# 2_cyber60-alps_matrix.net
KiCad netlist of a schematic drawn in Altium Designer
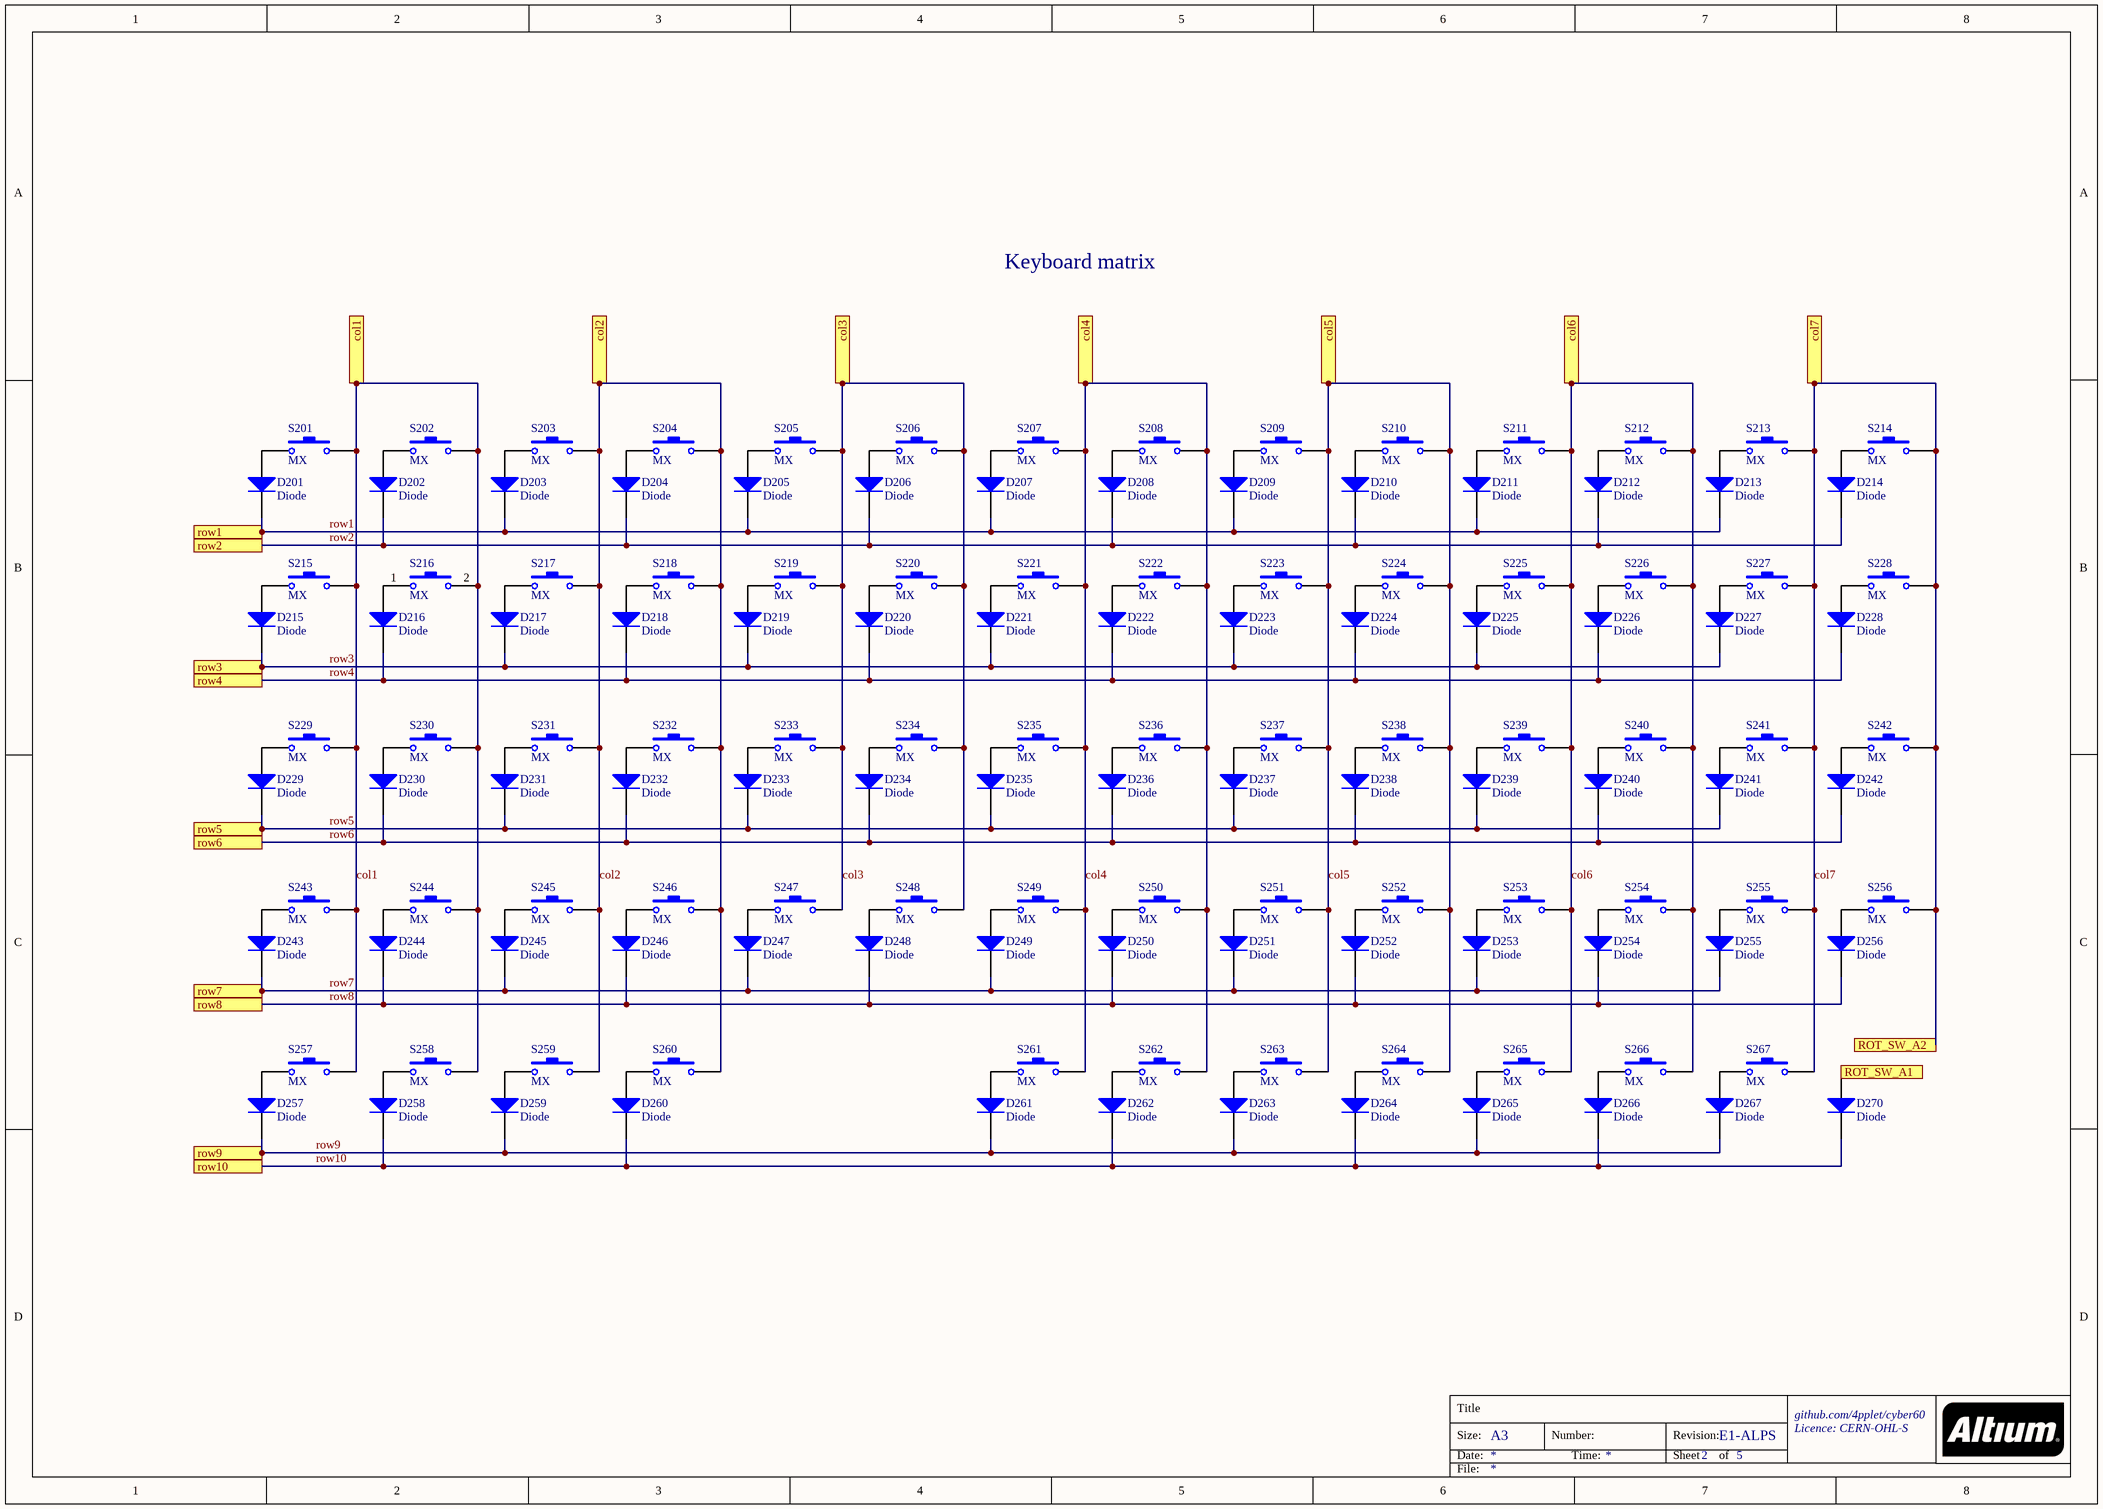
[diagram p0: 2_cyber60-alps_matrix.SchDoc]

(export (version "E")
  (design (tool "Eeschema 10.0.6"))
  (components
    (comp (ref "D201")
      (value "Diode")
      (footprint "SOD-123")
      (description "Default Diode")
      (fields (field (name "LCSC PART #") "C81598") (field (name "MRF.PART") "1N4148W"))
      (libsource (lib "Miscellaneous Devices") (part "Diode"))
    )
    (comp (ref "D202")
      (value "Diode")
      (footprint "SOD-123")
      (description "Default Diode")
      (fields (field (name "LCSC PART #") "C81598") (field (name "MRF.PART") "1N4148W"))
      (libsource (lib "Miscellaneous Devices") (part "Diode"))
    )
    (comp (ref "D203")
      (value "Diode")
      (footprint "SOD-123")
      (description "Default Diode")
      (fields (field (name "LCSC PART #") "C81598") (field (name "MRF.PART") "1N4148W"))
      (libsource (lib "Miscellaneous Devices") (part "Diode"))
    )
    (comp (ref "D204")
      (value "Diode")
      (footprint "SOD-123")
      (description "Default Diode")
      (fields (field (name "LCSC PART #") "C81598") (field (name "MRF.PART") "1N4148W"))
      (libsource (lib "Miscellaneous Devices") (part "Diode"))
    )
    (comp (ref "D205")
      (value "Diode")
      (footprint "SOD-123")
      (description "Default Diode")
      (fields (field (name "LCSC PART #") "C81598") (field (name "MRF.PART") "1N4148W"))
      (libsource (lib "Miscellaneous Devices") (part "Diode"))
    )
    (comp (ref "D206")
      (value "Diode")
      (footprint "SOD-123")
      (description "Default Diode")
      (fields (field (name "LCSC PART #") "C81598") (field (name "MRF.PART") "1N4148W"))
      (libsource (lib "Miscellaneous Devices") (part "Diode"))
    )
    (comp (ref "D207")
      (value "Diode")
      (footprint "SOD-123")
      (description "Default Diode")
      (fields (field (name "LCSC PART #") "C81598") (field (name "MRF.PART") "1N4148W"))
      (libsource (lib "Miscellaneous Devices") (part "Diode"))
    )
    (comp (ref "D208")
      (value "Diode")
      (footprint "SOD-123")
      (description "Default Diode")
      (fields (field (name "LCSC PART #") "C81598") (field (name "MRF.PART") "1N4148W"))
      (libsource (lib "Miscellaneous Devices") (part "Diode"))
    )
    (comp (ref "D209")
      (value "Diode")
      (footprint "SOD-123")
      (description "Default Diode")
      (fields (field (name "LCSC PART #") "C81598") (field (name "MRF.PART") "1N4148W"))
      (libsource (lib "Miscellaneous Devices") (part "Diode"))
    )
    (comp (ref "D210")
      (value "Diode")
      (footprint "SOD-123")
      (description "Default Diode")
      (fields (field (name "LCSC PART #") "C81598") (field (name "MRF.PART") "1N4148W"))
      (libsource (lib "Miscellaneous Devices") (part "Diode"))
    )
    (comp (ref "D211")
      (value "Diode")
      (footprint "SOD-123")
      (description "Default Diode")
      (fields (field (name "LCSC PART #") "C81598") (field (name "MRF.PART") "1N4148W"))
      (libsource (lib "Miscellaneous Devices") (part "Diode"))
    )
    (comp (ref "D212")
      (value "Diode")
      (footprint "SOD-123")
      (description "Default Diode")
      (fields (field (name "LCSC PART #") "C81598") (field (name "MRF.PART") "1N4148W"))
      (libsource (lib "Miscellaneous Devices") (part "Diode"))
    )
    (comp (ref "D213")
      (value "Diode")
      (footprint "SOD-123")
      (description "Default Diode")
      (fields (field (name "LCSC PART #") "C81598") (field (name "MRF.PART") "1N4148W"))
      (libsource (lib "Miscellaneous Devices") (part "Diode"))
    )
    (comp (ref "D214")
      (value "Diode")
      (footprint "SOD-123")
      (description "Default Diode")
      (fields (field (name "LCSC PART #") "C81598") (field (name "MRF.PART") "1N4148W"))
      (libsource (lib "Miscellaneous Devices") (part "Diode"))
    )
    (comp (ref "D215")
      (value "Diode")
      (footprint "SOD-123")
      (description "Default Diode")
      (fields (field (name "LCSC PART #") "C81598") (field (name "MRF.PART") "1N4148W"))
      (libsource (lib "Miscellaneous Devices") (part "Diode"))
    )
    (comp (ref "D216")
      (value "Diode")
      (footprint "SOD-123")
      (description "Default Diode")
      (fields (field (name "LCSC PART #") "C81598") (field (name "MRF.PART") "1N4148W"))
      (libsource (lib "Miscellaneous Devices") (part "Diode"))
    )
    (comp (ref "D217")
      (value "Diode")
      (footprint "SOD-123")
      (description "Default Diode")
      (fields (field (name "LCSC PART #") "C81598") (field (name "MRF.PART") "1N4148W"))
      (libsource (lib "Miscellaneous Devices") (part "Diode"))
    )
    (comp (ref "D218")
      (value "Diode")
      (footprint "SOD-123")
      (description "Default Diode")
      (fields (field (name "LCSC PART #") "C81598") (field (name "MRF.PART") "1N4148W"))
      (libsource (lib "Miscellaneous Devices") (part "Diode"))
    )
    (comp (ref "D219")
      (value "Diode")
      (footprint "SOD-123")
      (description "Default Diode")
      (fields (field (name "LCSC PART #") "C81598") (field (name "MRF.PART") "1N4148W"))
      (libsource (lib "Miscellaneous Devices") (part "Diode"))
    )
    (comp (ref "D220")
      (value "Diode")
      (footprint "SOD-123")
      (description "Default Diode")
      (fields (field (name "LCSC PART #") "C81598") (field (name "MRF.PART") "1N4148W"))
      (libsource (lib "Miscellaneous Devices") (part "Diode"))
    )
    (comp (ref "D221")
      (value "Diode")
      (footprint "SOD-123")
      (description "Default Diode")
      (fields (field (name "LCSC PART #") "C81598") (field (name "MRF.PART") "1N4148W"))
      (libsource (lib "Miscellaneous Devices") (part "Diode"))
    )
    (comp (ref "D222")
      (value "Diode")
      (footprint "SOD-123")
      (description "Default Diode")
      (fields (field (name "LCSC PART #") "C81598") (field (name "MRF.PART") "1N4148W"))
      (libsource (lib "Miscellaneous Devices") (part "Diode"))
    )
    (comp (ref "D223")
      (value "Diode")
      (footprint "SOD-123")
      (description "Default Diode")
      (fields (field (name "LCSC PART #") "C81598") (field (name "MRF.PART") "1N4148W"))
      (libsource (lib "Miscellaneous Devices") (part "Diode"))
    )
    (comp (ref "D224")
      (value "Diode")
      (footprint "SOD-123")
      (description "Default Diode")
      (fields (field (name "LCSC PART #") "C81598") (field (name "MRF.PART") "1N4148W"))
      (libsource (lib "Miscellaneous Devices") (part "Diode"))
    )
    (comp (ref "D225")
      (value "Diode")
      (footprint "SOD-123")
      (description "Default Diode")
      (fields (field (name "LCSC PART #") "C81598") (field (name "MRF.PART") "1N4148W"))
      (libsource (lib "Miscellaneous Devices") (part "Diode"))
    )
    (comp (ref "D226")
      (value "Diode")
      (footprint "SOD-123")
      (description "Default Diode")
      (fields (field (name "LCSC PART #") "C81598") (field (name "MRF.PART") "1N4148W"))
      (libsource (lib "Miscellaneous Devices") (part "Diode"))
    )
    (comp (ref "D227")
      (value "Diode")
      (footprint "SOD-123")
      (description "Default Diode")
      (fields (field (name "LCSC PART #") "C81598") (field (name "MRF.PART") "1N4148W"))
      (libsource (lib "Miscellaneous Devices") (part "Diode"))
    )
    (comp (ref "D228")
      (value "Diode")
      (footprint "SOD-123")
      (description "Default Diode")
      (fields (field (name "LCSC PART #") "C81598") (field (name "MRF.PART") "1N4148W"))
      (libsource (lib "Miscellaneous Devices") (part "Diode"))
    )
    (comp (ref "D229")
      (value "Diode")
      (footprint "SOD-123")
      (description "Default Diode")
      (fields (field (name "LCSC PART #") "C81598") (field (name "MRF.PART") "1N4148W"))
      (libsource (lib "Miscellaneous Devices") (part "Diode"))
    )
    (comp (ref "D230")
      (value "Diode")
      (footprint "SOD-123")
      (description "Default Diode")
      (fields (field (name "LCSC PART #") "C81598") (field (name "MRF.PART") "1N4148W"))
      (libsource (lib "Miscellaneous Devices") (part "Diode"))
    )
    (comp (ref "D231")
      (value "Diode")
      (footprint "SOD-123")
      (description "Default Diode")
      (fields (field (name "LCSC PART #") "C81598") (field (name "MRF.PART") "1N4148W"))
      (libsource (lib "Miscellaneous Devices") (part "Diode"))
    )
    (comp (ref "D232")
      (value "Diode")
      (footprint "SOD-123")
      (description "Default Diode")
      (fields (field (name "LCSC PART #") "C81598") (field (name "MRF.PART") "1N4148W"))
      (libsource (lib "Miscellaneous Devices") (part "Diode"))
    )
    (comp (ref "D233")
      (value "Diode")
      (footprint "SOD-123")
      (description "Default Diode")
      (fields (field (name "LCSC PART #") "C81598") (field (name "MRF.PART") "1N4148W"))
      (libsource (lib "Miscellaneous Devices") (part "Diode"))
    )
    (comp (ref "D234")
      (value "Diode")
      (footprint "SOD-123")
      (description "Default Diode")
      (fields (field (name "LCSC PART #") "C81598") (field (name "MRF.PART") "1N4148W"))
      (libsource (lib "Miscellaneous Devices") (part "Diode"))
    )
    (comp (ref "D235")
      (value "Diode")
      (footprint "SOD-123")
      (description "Default Diode")
      (fields (field (name "LCSC PART #") "C81598") (field (name "MRF.PART") "1N4148W"))
      (libsource (lib "Miscellaneous Devices") (part "Diode"))
    )
    (comp (ref "D236")
      (value "Diode")
      (footprint "SOD-123")
      (description "Default Diode")
      (fields (field (name "LCSC PART #") "C81598") (field (name "MRF.PART") "1N4148W"))
      (libsource (lib "Miscellaneous Devices") (part "Diode"))
    )
    (comp (ref "D237")
      (value "Diode")
      (footprint "SOD-123")
      (description "Default Diode")
      (fields (field (name "LCSC PART #") "C81598") (field (name "MRF.PART") "1N4148W"))
      (libsource (lib "Miscellaneous Devices") (part "Diode"))
    )
    (comp (ref "D238")
      (value "Diode")
      (footprint "SOD-123")
      (description "Default Diode")
      (fields (field (name "LCSC PART #") "C81598") (field (name "MRF.PART") "1N4148W"))
      (libsource (lib "Miscellaneous Devices") (part "Diode"))
    )
    (comp (ref "D239")
      (value "Diode")
      (footprint "SOD-123")
      (description "Default Diode")
      (fields (field (name "LCSC PART #") "C81598") (field (name "MRF.PART") "1N4148W"))
      (libsource (lib "Miscellaneous Devices") (part "Diode"))
    )
    (comp (ref "D240")
      (value "Diode")
      (footprint "SOD-123")
      (description "Default Diode")
      (fields (field (name "LCSC PART #") "C81598") (field (name "MRF.PART") "1N4148W"))
      (libsource (lib "Miscellaneous Devices") (part "Diode"))
    )
    (comp (ref "D241")
      (value "Diode")
      (footprint "SOD-123")
      (description "Default Diode")
      (fields (field (name "LCSC PART #") "C81598") (field (name "MRF.PART") "1N4148W"))
      (libsource (lib "Miscellaneous Devices") (part "Diode"))
    )
    (comp (ref "D242")
      (value "Diode")
      (footprint "SOD-123")
      (description "Default Diode")
      (fields (field (name "LCSC PART #") "C81598") (field (name "MRF.PART") "1N4148W"))
      (libsource (lib "Miscellaneous Devices") (part "Diode"))
    )
    (comp (ref "D243")
      (value "Diode")
      (footprint "SOD-123")
      (description "Default Diode")
      (fields (field (name "LCSC PART #") "C81598") (field (name "MRF.PART") "1N4148W"))
      (libsource (lib "Miscellaneous Devices") (part "Diode"))
    )
    (comp (ref "D244")
      (value "Diode")
      (footprint "SOD-123")
      (description "Default Diode")
      (fields (field (name "LCSC PART #") "C81598") (field (name "MRF.PART") "1N4148W"))
      (libsource (lib "Miscellaneous Devices") (part "Diode"))
    )
    (comp (ref "D245")
      (value "Diode")
      (footprint "SOD-123")
      (description "Default Diode")
      (fields (field (name "LCSC PART #") "C81598") (field (name "MRF.PART") "1N4148W"))
      (libsource (lib "Miscellaneous Devices") (part "Diode"))
    )
    (comp (ref "D246")
      (value "Diode")
      (footprint "SOD-123")
      (description "Default Diode")
      (fields (field (name "LCSC PART #") "C81598") (field (name "MRF.PART") "1N4148W"))
      (libsource (lib "Miscellaneous Devices") (part "Diode"))
    )
    (comp (ref "D247")
      (value "Diode")
      (footprint "SOD-123")
      (description "Default Diode")
      (fields (field (name "LCSC PART #") "C81598") (field (name "MRF.PART") "1N4148W"))
      (libsource (lib "Miscellaneous Devices") (part "Diode"))
    )
    (comp (ref "D248")
      (value "Diode")
      (footprint "SOD-123")
      (description "Default Diode")
      (fields (field (name "LCSC PART #") "C81598") (field (name "MRF.PART") "1N4148W"))
      (libsource (lib "Miscellaneous Devices") (part "Diode"))
    )
    (comp (ref "D249")
      (value "Diode")
      (footprint "SOD-123")
      (description "Default Diode")
      (fields (field (name "LCSC PART #") "C81598") (field (name "MRF.PART") "1N4148W"))
      (libsource (lib "Miscellaneous Devices") (part "Diode"))
    )
    (comp (ref "D250")
      (value "Diode")
      (footprint "SOD-123")
      (description "Default Diode")
      (fields (field (name "LCSC PART #") "C81598") (field (name "MRF.PART") "1N4148W"))
      (libsource (lib "Miscellaneous Devices") (part "Diode"))
    )
    (comp (ref "D251")
      (value "Diode")
      (footprint "SOD-123")
      (description "Default Diode")
      (fields (field (name "LCSC PART #") "C81598") (field (name "MRF.PART") "1N4148W"))
      (libsource (lib "Miscellaneous Devices") (part "Diode"))
    )
    (comp (ref "D252")
      (value "Diode")
      (footprint "SOD-123")
      (description "Default Diode")
      (fields (field (name "LCSC PART #") "C81598") (field (name "MRF.PART") "1N4148W"))
      (libsource (lib "Miscellaneous Devices") (part "Diode"))
    )
    (comp (ref "D253")
      (value "Diode")
      (footprint "SOD-123")
      (description "Default Diode")
      (fields (field (name "LCSC PART #") "C81598") (field (name "MRF.PART") "1N4148W"))
      (libsource (lib "Miscellaneous Devices") (part "Diode"))
    )
    (comp (ref "D254")
      (value "Diode")
      (footprint "SOD-123")
      (description "Default Diode")
      (fields (field (name "LCSC PART #") "C81598") (field (name "MRF.PART") "1N4148W"))
      (libsource (lib "Miscellaneous Devices") (part "Diode"))
    )
    (comp (ref "D255")
      (value "Diode")
      (footprint "SOD-123")
      (description "Default Diode")
      (fields (field (name "LCSC PART #") "C81598") (field (name "MRF.PART") "1N4148W"))
      (libsource (lib "Miscellaneous Devices") (part "Diode"))
    )
    (comp (ref "D256")
      (value "Diode")
      (footprint "SOD-123")
      (description "Default Diode")
      (fields (field (name "LCSC PART #") "C81598") (field (name "MRF.PART") "1N4148W"))
      (libsource (lib "Miscellaneous Devices") (part "Diode"))
    )
    (comp (ref "D257")
      (value "Diode")
      (footprint "SOD-123")
      (description "Default Diode")
      (fields (field (name "LCSC PART #") "C81598") (field (name "MRF.PART") "1N4148W"))
      (libsource (lib "Miscellaneous Devices") (part "Diode"))
    )
    (comp (ref "D258")
      (value "Diode")
      (footprint "SOD-123")
      (description "Default Diode")
      (fields (field (name "LCSC PART #") "C81598") (field (name "MRF.PART") "1N4148W"))
      (libsource (lib "Miscellaneous Devices") (part "Diode"))
    )
    (comp (ref "D259")
      (value "Diode")
      (footprint "SOD-123")
      (description "Default Diode")
      (fields (field (name "LCSC PART #") "C81598") (field (name "MRF.PART") "1N4148W"))
      (libsource (lib "Miscellaneous Devices") (part "Diode"))
    )
    (comp (ref "D260")
      (value "Diode")
      (footprint "SOD-123")
      (description "Default Diode")
      (fields (field (name "LCSC PART #") "C81598") (field (name "MRF.PART") "1N4148W"))
      (libsource (lib "Miscellaneous Devices") (part "Diode"))
    )
    (comp (ref "D261")
      (value "Diode")
      (footprint "SOD-123")
      (description "Default Diode")
      (fields (field (name "LCSC PART #") "C81598") (field (name "MRF.PART") "1N4148W"))
      (libsource (lib "Miscellaneous Devices") (part "Diode"))
    )
    (comp (ref "D262")
      (value "Diode")
      (footprint "SOD-123")
      (description "Default Diode")
      (fields (field (name "LCSC PART #") "C81598") (field (name "MRF.PART") "1N4148W"))
      (libsource (lib "Miscellaneous Devices") (part "Diode"))
    )
    (comp (ref "D263")
      (value "Diode")
      (footprint "SOD-123")
      (description "Default Diode")
      (fields (field (name "LCSC PART #") "C81598") (field (name "MRF.PART") "1N4148W"))
      (libsource (lib "Miscellaneous Devices") (part "Diode"))
    )
    (comp (ref "D264")
      (value "Diode")
      (footprint "SOD-123")
      (description "Default Diode")
      (fields (field (name "LCSC PART #") "C81598") (field (name "MRF.PART") "1N4148W"))
      (libsource (lib "Miscellaneous Devices") (part "Diode"))
    )
    (comp (ref "D265")
      (value "Diode")
      (footprint "SOD-123")
      (description "Default Diode")
      (fields (field (name "LCSC PART #") "C81598") (field (name "MRF.PART") "1N4148W"))
      (libsource (lib "Miscellaneous Devices") (part "Diode"))
    )
    (comp (ref "D266")
      (value "Diode")
      (footprint "SOD-123")
      (description "Default Diode")
      (fields (field (name "LCSC PART #") "C81598") (field (name "MRF.PART") "1N4148W"))
      (libsource (lib "Miscellaneous Devices") (part "Diode"))
    )
    (comp (ref "D267")
      (value "Diode")
      (footprint "SOD-123")
      (description "Default Diode")
      (fields (field (name "LCSC PART #") "C81598") (field (name "MRF.PART") "1N4148W"))
      (libsource (lib "Miscellaneous Devices") (part "Diode"))
    )
    (comp (ref "D270")
      (value "Diode")
      (footprint "SOD-123")
      (description "Default Diode")
      (fields (field (name "LCSC PART #") "C81598") (field (name "MRF.PART") "1N4148W"))
      (libsource (lib "Miscellaneous Devices") (part "Diode"))
    )
    (comp (ref "S201")
      (value "MX")
      (footprint "Alps-switch - switched pol")
      (description "Switch")
      (libsource (lib "Miscellaneous Devices") (part "SW-PB"))
    )
    (comp (ref "S202")
      (value "MX")
      (footprint "Alps-switch - switched pol")
      (description "Switch")
      (libsource (lib "Miscellaneous Devices") (part "SW-PB"))
    )
    (comp (ref "S203")
      (value "MX")
      (footprint "Alps-switch - switched pol")
      (description "Switch")
      (libsource (lib "Miscellaneous Devices") (part "SW-PB"))
    )
    (comp (ref "S204")
      (value "MX")
      (footprint "Alps-switch")
      (description "Switch")
      (libsource (lib "Miscellaneous Devices") (part "SW-PB"))
    )
    (comp (ref "S205")
      (value "MX")
      (footprint "Alps-switch - switched pol")
      (description "Switch")
      (libsource (lib "Miscellaneous Devices") (part "SW-PB"))
    )
    (comp (ref "S206")
      (value "MX")
      (footprint "Alps-switch - switched pol")
      (description "Switch")
      (libsource (lib "Miscellaneous Devices") (part "SW-PB"))
    )
    (comp (ref "S207")
      (value "MX")
      (footprint "Alps-switch - switched pol")
      (description "Switch")
      (libsource (lib "Miscellaneous Devices") (part "SW-PB"))
    )
    (comp (ref "S208")
      (value "MX")
      (footprint "Alps-switch - switched pol")
      (description "Switch")
      (libsource (lib "Miscellaneous Devices") (part "SW-PB"))
    )
    (comp (ref "S209")
      (value "MX")
      (footprint "Alps-switch - switched pol")
      (description "Switch")
      (libsource (lib "Miscellaneous Devices") (part "SW-PB"))
    )
    (comp (ref "S210")
      (value "MX")
      (footprint "Alps-switch - switched pol")
      (description "Switch")
      (libsource (lib "Miscellaneous Devices") (part "SW-PB"))
    )
    (comp (ref "S211")
      (value "MX")
      (footprint "Alps-switch - switched pol")
      (description "Switch")
      (libsource (lib "Miscellaneous Devices") (part "SW-PB"))
    )
    (comp (ref "S212")
      (value "MX")
      (footprint "Alps-switch - switched pol")
      (description "Switch")
      (libsource (lib "Miscellaneous Devices") (part "SW-PB"))
    )
    (comp (ref "S213")
      (value "MX")
      (footprint "Alps-switch - switched pol")
      (description "Switch")
      (libsource (lib "Miscellaneous Devices") (part "SW-PB"))
    )
    (comp (ref "S214")
      (value "MX")
      (footprint "Alps-switch - switched pol")
      (description "Switch")
      (libsource (lib "Miscellaneous Devices") (part "SW-PB"))
    )
    (comp (ref "S215")
      (value "MX")
      (footprint "Alps-switch - switched pol")
      (description "TAB")
      (libsource (lib "Miscellaneous Devices") (part "SW-PB"))
    )
    (comp (ref "S216")
      (value "MX")
      (footprint "Alps-switch - switched pol")
      (description "Switch")
      (libsource (lib "") (part "SW-PB_1"))
    )
    (comp (ref "S217")
      (value "MX")
      (footprint "Alps-switch - switched pol")
      (description "Switch")
      (libsource (lib "Miscellaneous Devices") (part "SW-PB"))
    )
    (comp (ref "S218")
      (value "MX")
      (footprint "Alps-switch - switched pol")
      (description "Switch")
      (libsource (lib "Miscellaneous Devices") (part "SW-PB"))
    )
    (comp (ref "S219")
      (value "MX")
      (footprint "Alps-switch - switched pol")
      (description "Switch")
      (libsource (lib "Miscellaneous Devices") (part "SW-PB"))
    )
    (comp (ref "S220")
      (value "MX")
      (footprint "Alps-switch")
      (description "Switch")
      (libsource (lib "Miscellaneous Devices") (part "SW-PB"))
    )
    (comp (ref "S221")
      (value "MX")
      (footprint "Alps-switch - switched pol")
      (description "Switch")
      (libsource (lib "Miscellaneous Devices") (part "SW-PB"))
    )
    (comp (ref "S222")
      (value "MX")
      (footprint "Alps-switch - switched pol")
      (description "Switch")
      (libsource (lib "Miscellaneous Devices") (part "SW-PB"))
    )
    (comp (ref "S223")
      (value "MX")
      (footprint "Alps-switch - switched pol")
      (description "Switch")
      (libsource (lib "Miscellaneous Devices") (part "SW-PB"))
    )
    (comp (ref "S224")
      (value "MX")
      (footprint "Alps-switch - switched pol")
      (description "Switch")
      (libsource (lib "Miscellaneous Devices") (part "SW-PB"))
    )
    (comp (ref "S225")
      (value "MX")
      (footprint "Alps-switch - switched pol")
      (description "Switch")
      (libsource (lib "Miscellaneous Devices") (part "SW-PB"))
    )
    (comp (ref "S226")
      (value "MX")
      (footprint "Alps-switch")
      (description "Switch")
      (libsource (lib "Miscellaneous Devices") (part "SW-PB"))
    )
    (comp (ref "S227")
      (value "MX")
      (footprint "Alps-switch")
      (description "Switch")
      (libsource (lib "Miscellaneous Devices") (part "SW-PB"))
    )
    (comp (ref "S228")
      (value "MX")
      (footprint "ALPS-switch - backspace")
      (description "Switch")
      (libsource (lib "Miscellaneous Devices") (part "SW-PB"))
    )
    (comp (ref "S229")
      (value "MX")
      (footprint "ALPS-switch - CAPS")
      (description "Switch")
      (libsource (lib "Miscellaneous Devices") (part "SW-PB"))
    )
    (comp (ref "S230")
      (value "MX")
      (footprint "Alps-switch - switched pol")
      (description "Switch")
      (libsource (lib "Miscellaneous Devices") (part "SW-PB"))
    )
    (comp (ref "S231")
      (value "MX")
      (footprint "Alps-switch - switched pol")
      (description "Switch")
      (libsource (lib "Miscellaneous Devices") (part "SW-PB"))
    )
    (comp (ref "S232")
      (value "MX")
      (footprint "Alps-switch - switched pol")
      (description "Switch")
      (libsource (lib "Miscellaneous Devices") (part "SW-PB"))
    )
    (comp (ref "S233")
      (value "MX")
      (footprint "Alps-switch - switched pol")
      (description "Switch")
      (libsource (lib "Miscellaneous Devices") (part "SW-PB"))
    )
    (comp (ref "S234")
      (value "MX")
      (footprint "Alps-switch")
      (description "Switch")
      (libsource (lib "Miscellaneous Devices") (part "SW-PB"))
    )
    (comp (ref "S235")
      (value "MX")
      (footprint "Alps-switch - switched pol")
      (description "Switch")
      (libsource (lib "Miscellaneous Devices") (part "SW-PB"))
    )
    (comp (ref "S236")
      (value "MX")
      (footprint "Alps-switch - switched pol")
      (description "Switch")
      (libsource (lib "Miscellaneous Devices") (part "SW-PB"))
    )
    (comp (ref "S237")
      (value "MX")
      (footprint "Alps-switch - switched pol")
      (description "Switch")
      (libsource (lib "Miscellaneous Devices") (part "SW-PB"))
    )
    (comp (ref "S238")
      (value "MX")
      (footprint "Alps-switch - switched pol")
      (description "Switch")
      (libsource (lib "Miscellaneous Devices") (part "SW-PB"))
    )
    (comp (ref "S239")
      (value "MX")
      (footprint "Alps-switch")
      (description "Switch")
      (libsource (lib "Miscellaneous Devices") (part "SW-PB"))
    )
    (comp (ref "S240")
      (value "MX")
      (footprint "Alps-switch - switched pol")
      (description "Switch")
      (libsource (lib "Miscellaneous Devices") (part "SW-PB"))
    )
    (comp (ref "S241")
      (value "MX")
      (footprint "Alps-switch")
      (description "Switch")
      (libsource (lib "Miscellaneous Devices") (part "SW-PB"))
    )
    (comp (ref "S242")
      (value "MX")
      (footprint "ALPS-switch - 1.5U")
      (description "Switch")
      (libsource (lib "Miscellaneous Devices") (part "SW-PB"))
    )
    (comp (ref "S243")
      (value "MX")
      (footprint "ALPS-switch - Left shift v2")
      (description "Switch")
      (libsource (lib "Miscellaneous Devices") (part "SW-PB"))
    )
    (comp (ref "S244")
      (value "MX")
      (footprint "Alps-switch - switched pol")
      (description "Switch")
      (libsource (lib "Miscellaneous Devices") (part "SW-PB"))
    )
    (comp (ref "S245")
      (value "MX")
      (footprint "Alps-switch - switched pol")
      (description "Switch")
      (libsource (lib "Miscellaneous Devices") (part "SW-PB"))
    )
    (comp (ref "S246")
      (value "MX")
      (footprint "Alps-switch - switched pol")
      (description "Switch")
      (libsource (lib "Miscellaneous Devices") (part "SW-PB"))
    )
    (comp (ref "S247")
      (value "MX")
      (footprint "Alps-switch - switched pol")
      (description "Switch")
      (libsource (lib "Miscellaneous Devices") (part "SW-PB"))
    )
    (comp (ref "S248")
      (value "MX")
      (footprint "Alps-switch")
      (description "Switch")
      (libsource (lib "Miscellaneous Devices") (part "SW-PB"))
    )
    (comp (ref "S249")
      (value "MX")
      (footprint "Alps-switch - switched pol")
      (description "Switch")
      (libsource (lib "Miscellaneous Devices") (part "SW-PB"))
    )
    (comp (ref "S250")
      (value "MX")
      (footprint "Alps-switch - switched pol")
      (description "Switch")
      (libsource (lib "Miscellaneous Devices") (part "SW-PB"))
    )
    (comp (ref "S251")
      (value "MX")
      (footprint "Alps-switch - switched pol")
      (description "Switch")
      (libsource (lib "Miscellaneous Devices") (part "SW-PB"))
    )
    (comp (ref "S252")
      (value "MX")
      (footprint "Alps-switch - switched pol")
      (description "Switch")
      (libsource (lib "Miscellaneous Devices") (part "SW-PB"))
    )
    (comp (ref "S253")
      (value "MX")
      (footprint "Alps-switch - switched pol")
      (description "Switch")
      (libsource (lib "Miscellaneous Devices") (part "SW-PB"))
    )
    (comp (ref "S254")
      (value "MX")
      (footprint "Alps-switch - switched pol")
      (description "Switch")
      (libsource (lib "Miscellaneous Devices") (part "SW-PB"))
    )
    (comp (ref "S255")
      (value "MX")
      (footprint "Alps-switch")
      (description "Switch")
      (libsource (lib "Miscellaneous Devices") (part "SW-PB"))
    )
    (comp (ref "S256")
      (value "MX")
      (footprint "ALPS-switch - Enter - rotated stab")
      (description "Switch")
      (libsource (lib "Miscellaneous Devices") (part "SW-PB"))
    )
    (comp (ref "S257")
      (value "MX")
      (footprint "ALPS-switch - 1.5u MOD-L")
      (description "Switch")
      (libsource (lib "Miscellaneous Devices") (part "SW-PB"))
    )
    (comp (ref "S258")
      (value "MX")
      (footprint "ALPS-switch - L_WIN - V3")
      (description "Switch")
      (libsource (lib "Miscellaneous Devices") (part "SW-PB"))
    )
    (comp (ref "S259")
      (value "MX")
      (footprint "ALPS-SWITCH - L_ALT - V3")
      (description "Switch")
      (libsource (lib "Miscellaneous Devices") (part "SW-PB"))
    )
    (comp (ref "S260")
      (value "MX")
      (footprint "ALPS-switch - 2.75U - Rotated stab")
      (description "Switch")
      (libsource (lib "Miscellaneous Devices") (part "SW-PB"))
    )
    (comp (ref "S261")
      (value "MX")
      (footprint "ALPS-switch - Space_V2")
      (description "Switch")
      (libsource (lib "Miscellaneous Devices") (part "SW-PB"))
    )
    (comp (ref "S262")
      (value "MX")
      (footprint "ALPS-switch - 2.75U - Rotated stab")
      (description "Switch")
      (libsource (lib "Miscellaneous Devices") (part "SW-PB"))
    )
    (comp (ref "S263")
      (value "MX")
      (footprint "Alps-switch - switched pol")
      (description "Switch")
      (libsource (lib "Miscellaneous Devices") (part "SW-PB"))
    )
    (comp (ref "S264")
      (value "MX")
      (footprint "ALPS-SWITCH - R_ALT - V3")
      (description "Switch")
      (libsource (lib "Miscellaneous Devices") (part "SW-PB"))
    )
    (comp (ref "S265")
      (value "MX")
      (footprint "ALPS-switch - R_WIN V3")
      (description "Switch")
      (libsource (lib "Miscellaneous Devices") (part "SW-PB"))
    )
    (comp (ref "S266")
      (value "MX")
      (footprint "ALPS-switch - 1.5u MOD-R")
      (description "Switch")
      (libsource (lib "Miscellaneous Devices") (part "SW-PB"))
    )
    (comp (ref "S267")
      (value "MX")
      (footprint "ALPS-switch - right shift - stabs")
      (description "Switch")
      (libsource (lib "Miscellaneous Devices") (part "SW-PB"))
    )
  )
  (nets
    (net (code "1") (name "/ROT_SW_A1") (class "Default")
      (node (ref "D270") (pin "1") (pinfunction "A_1") (pintype "passive"))
    )
    (net (code "2") (name "/col1") (class "Default")
      (node (ref "S201") (pin "2") (pinfunction "2_2") (pintype "passive"))
      (node (ref "S202") (pin "2") (pinfunction "2_2") (pintype "passive"))
      (node (ref "S215") (pin "2") (pinfunction "2_2") (pintype "passive"))
      (node (ref "S216") (pin "2") (pinfunction "2_2") (pintype "passive"))
      (node (ref "S229") (pin "2") (pinfunction "2_2") (pintype "passive"))
      (node (ref "S230") (pin "2") (pinfunction "2_2") (pintype "passive"))
      (node (ref "S243") (pin "2") (pinfunction "2_2") (pintype "passive"))
      (node (ref "S244") (pin "2") (pinfunction "2_2") (pintype "passive"))
      (node (ref "S257") (pin "1") (pinfunction "1_1") (pintype "passive"))
      (node (ref "S258") (pin "2") (pinfunction "2_2") (pintype "passive"))
    )
    (net (code "3") (name "/col2") (class "Default")
      (node (ref "S203") (pin "2") (pinfunction "2_2") (pintype "passive"))
      (node (ref "S204") (pin "2") (pinfunction "2_2") (pintype "passive"))
      (node (ref "S217") (pin "2") (pinfunction "2_2") (pintype "passive"))
      (node (ref "S218") (pin "2") (pinfunction "2_2") (pintype "passive"))
      (node (ref "S231") (pin "2") (pinfunction "2_2") (pintype "passive"))
      (node (ref "S232") (pin "2") (pinfunction "2_2") (pintype "passive"))
      (node (ref "S245") (pin "2") (pinfunction "2_2") (pintype "passive"))
      (node (ref "S246") (pin "2") (pinfunction "2_2") (pintype "passive"))
      (node (ref "S259") (pin "2") (pinfunction "2_2") (pintype "passive"))
      (node (ref "S260") (pin "2") (pinfunction "2_2") (pintype "passive"))
    )
    (net (code "4") (name "/col3") (class "Default")
      (node (ref "S205") (pin "2") (pinfunction "2_2") (pintype "passive"))
      (node (ref "S206") (pin "2") (pinfunction "2_2") (pintype "passive"))
      (node (ref "S219") (pin "2") (pinfunction "2_2") (pintype "passive"))
      (node (ref "S220") (pin "2") (pinfunction "2_2") (pintype "passive"))
      (node (ref "S233") (pin "2") (pinfunction "2_2") (pintype "passive"))
      (node (ref "S234") (pin "2") (pinfunction "2_2") (pintype "passive"))
      (node (ref "S247") (pin "2") (pinfunction "2_2") (pintype "passive"))
      (node (ref "S248") (pin "2") (pinfunction "2_2") (pintype "passive"))
    )
    (net (code "5") (name "/col4") (class "Default")
      (node (ref "S207") (pin "2") (pinfunction "2_2") (pintype "passive"))
      (node (ref "S208") (pin "2") (pinfunction "2_2") (pintype "passive"))
      (node (ref "S221") (pin "2") (pinfunction "2_2") (pintype "passive"))
      (node (ref "S222") (pin "2") (pinfunction "2_2") (pintype "passive"))
      (node (ref "S235") (pin "2") (pinfunction "2_2") (pintype "passive"))
      (node (ref "S236") (pin "2") (pinfunction "2_2") (pintype "passive"))
      (node (ref "S249") (pin "2") (pinfunction "2_2") (pintype "passive"))
      (node (ref "S250") (pin "2") (pinfunction "2_2") (pintype "passive"))
      (node (ref "S261") (pin "1") (pinfunction "1_1") (pintype "passive"))
      (node (ref "S262") (pin "2") (pinfunction "2_2") (pintype "passive"))
    )
    (net (code "6") (name "/col5") (class "Default")
      (node (ref "S209") (pin "2") (pinfunction "2_2") (pintype "passive"))
      (node (ref "S210") (pin "2") (pinfunction "2_2") (pintype "passive"))
      (node (ref "S223") (pin "2") (pinfunction "2_2") (pintype "passive"))
      (node (ref "S224") (pin "2") (pinfunction "2_2") (pintype "passive"))
      (node (ref "S237") (pin "2") (pinfunction "2_2") (pintype "passive"))
      (node (ref "S238") (pin "2") (pinfunction "2_2") (pintype "passive"))
      (node (ref "S251") (pin "2") (pinfunction "2_2") (pintype "passive"))
      (node (ref "S252") (pin "2") (pinfunction "2_2") (pintype "passive"))
      (node (ref "S263") (pin "2") (pinfunction "2_2") (pintype "passive"))
      (node (ref "S264") (pin "1") (pinfunction "1_1") (pintype "passive"))
    )
    (net (code "7") (name "/col6") (class "Default")
      (node (ref "S211") (pin "2") (pinfunction "2_2") (pintype "passive"))
      (node (ref "S212") (pin "2") (pinfunction "2_2") (pintype "passive"))
      (node (ref "S225") (pin "2") (pinfunction "2_2") (pintype "passive"))
      (node (ref "S226") (pin "2") (pinfunction "2_2") (pintype "passive"))
      (node (ref "S239") (pin "2") (pinfunction "2_2") (pintype "passive"))
      (node (ref "S240") (pin "2") (pinfunction "2_2") (pintype "passive"))
      (node (ref "S253") (pin "2") (pinfunction "2_2") (pintype "passive"))
      (node (ref "S254") (pin "2") (pinfunction "2_2") (pintype "passive"))
      (node (ref "S265") (pin "2") (pinfunction "2_2") (pintype "passive"))
      (node (ref "S266") (pin "2") (pinfunction "2_2") (pintype "passive"))
    )
    (net (code "8") (name "/col7") (class "Default")
      (node (ref "S213") (pin "2") (pinfunction "2_2") (pintype "passive"))
      (node (ref "S214") (pin "2") (pinfunction "2_2") (pintype "passive"))
      (node (ref "S227") (pin "2") (pinfunction "2_2") (pintype "passive"))
      (node (ref "S228") (pin "1") (pinfunction "1_1") (pintype "passive"))
      (node (ref "S241") (pin "2") (pinfunction "2_2") (pintype "passive"))
      (node (ref "S242") (pin "2") (pinfunction "2_2") (pintype "passive"))
      (node (ref "S255") (pin "2") (pinfunction "2_2") (pintype "passive"))
      (node (ref "S256") (pin "2") (pinfunction "2_2") (pintype "passive"))
      (node (ref "S267") (pin "1") (pinfunction "1_1") (pintype "passive"))
    )
    (net (code "9") (name "/row1") (class "Default")
      (node (ref "D201") (pin "2") (pinfunction "K_2") (pintype "passive"))
      (node (ref "D203") (pin "2") (pinfunction "K_2") (pintype "passive"))
      (node (ref "D205") (pin "2") (pinfunction "K_2") (pintype "passive"))
      (node (ref "D207") (pin "2") (pinfunction "K_2") (pintype "passive"))
      (node (ref "D209") (pin "2") (pinfunction "K_2") (pintype "passive"))
      (node (ref "D211") (pin "2") (pinfunction "K_2") (pintype "passive"))
      (node (ref "D213") (pin "2") (pinfunction "K_2") (pintype "passive"))
    )
    (net (code "10") (name "/row2") (class "Default")
      (node (ref "D202") (pin "2") (pinfunction "K_2") (pintype "passive"))
      (node (ref "D204") (pin "2") (pinfunction "K_2") (pintype "passive"))
      (node (ref "D206") (pin "2") (pinfunction "K_2") (pintype "passive"))
      (node (ref "D208") (pin "2") (pinfunction "K_2") (pintype "passive"))
      (node (ref "D210") (pin "2") (pinfunction "K_2") (pintype "passive"))
      (node (ref "D212") (pin "2") (pinfunction "K_2") (pintype "passive"))
      (node (ref "D214") (pin "2") (pinfunction "K_2") (pintype "passive"))
    )
    (net (code "11") (name "/row3") (class "Default")
      (node (ref "D215") (pin "2") (pinfunction "K_2") (pintype "passive"))
      (node (ref "D217") (pin "2") (pinfunction "K_2") (pintype "passive"))
      (node (ref "D219") (pin "2") (pinfunction "K_2") (pintype "passive"))
      (node (ref "D221") (pin "2") (pinfunction "K_2") (pintype "passive"))
      (node (ref "D223") (pin "2") (pinfunction "K_2") (pintype "passive"))
      (node (ref "D225") (pin "2") (pinfunction "K_2") (pintype "passive"))
      (node (ref "D227") (pin "2") (pinfunction "K_2") (pintype "passive"))
    )
    (net (code "12") (name "/row4") (class "Default")
      (node (ref "D216") (pin "2") (pinfunction "K_2") (pintype "passive"))
      (node (ref "D218") (pin "2") (pinfunction "K_2") (pintype "passive"))
      (node (ref "D220") (pin "2") (pinfunction "K_2") (pintype "passive"))
      (node (ref "D222") (pin "2") (pinfunction "K_2") (pintype "passive"))
      (node (ref "D224") (pin "2") (pinfunction "K_2") (pintype "passive"))
      (node (ref "D226") (pin "2") (pinfunction "K_2") (pintype "passive"))
      (node (ref "D228") (pin "2") (pinfunction "K_2") (pintype "passive"))
    )
    (net (code "13") (name "/row5") (class "Default")
      (node (ref "D229") (pin "2") (pinfunction "K_2") (pintype "passive"))
      (node (ref "D231") (pin "2") (pinfunction "K_2") (pintype "passive"))
      (node (ref "D233") (pin "2") (pinfunction "K_2") (pintype "passive"))
      (node (ref "D235") (pin "2") (pinfunction "K_2") (pintype "passive"))
      (node (ref "D237") (pin "2") (pinfunction "K_2") (pintype "passive"))
      (node (ref "D239") (pin "2") (pinfunction "K_2") (pintype "passive"))
      (node (ref "D241") (pin "2") (pinfunction "K_2") (pintype "passive"))
    )
    (net (code "14") (name "/row6") (class "Default")
      (node (ref "D230") (pin "2") (pinfunction "K_2") (pintype "passive"))
      (node (ref "D232") (pin "2") (pinfunction "K_2") (pintype "passive"))
      (node (ref "D234") (pin "2") (pinfunction "K_2") (pintype "passive"))
      (node (ref "D236") (pin "2") (pinfunction "K_2") (pintype "passive"))
      (node (ref "D238") (pin "2") (pinfunction "K_2") (pintype "passive"))
      (node (ref "D240") (pin "2") (pinfunction "K_2") (pintype "passive"))
      (node (ref "D242") (pin "2") (pinfunction "K_2") (pintype "passive"))
    )
    (net (code "15") (name "/row7") (class "Default")
      (node (ref "D243") (pin "2") (pinfunction "K_2") (pintype "passive"))
      (node (ref "D245") (pin "2") (pinfunction "K_2") (pintype "passive"))
      (node (ref "D247") (pin "2") (pinfunction "K_2") (pintype "passive"))
      (node (ref "D249") (pin "2") (pinfunction "K_2") (pintype "passive"))
      (node (ref "D251") (pin "2") (pinfunction "K_2") (pintype "passive"))
      (node (ref "D253") (pin "2") (pinfunction "K_2") (pintype "passive"))
      (node (ref "D255") (pin "2") (pinfunction "K_2") (pintype "passive"))
    )
    (net (code "16") (name "/row8") (class "Default")
      (node (ref "D244") (pin "2") (pinfunction "K_2") (pintype "passive"))
      (node (ref "D246") (pin "2") (pinfunction "K_2") (pintype "passive"))
      (node (ref "D248") (pin "2") (pinfunction "K_2") (pintype "passive"))
      (node (ref "D250") (pin "2") (pinfunction "K_2") (pintype "passive"))
      (node (ref "D252") (pin "2") (pinfunction "K_2") (pintype "passive"))
      (node (ref "D254") (pin "2") (pinfunction "K_2") (pintype "passive"))
      (node (ref "D256") (pin "2") (pinfunction "K_2") (pintype "passive"))
    )
    (net (code "17") (name "/row9") (class "Default")
      (node (ref "D257") (pin "2") (pinfunction "K_2") (pintype "passive"))
      (node (ref "D259") (pin "2") (pinfunction "K_2") (pintype "passive"))
      (node (ref "D261") (pin "2") (pinfunction "K_2") (pintype "passive"))
      (node (ref "D263") (pin "2") (pinfunction "K_2") (pintype "passive"))
      (node (ref "D265") (pin "2") (pinfunction "K_2") (pintype "passive"))
      (node (ref "D267") (pin "2") (pinfunction "K_2") (pintype "passive"))
    )
    (net (code "18") (name "/row10") (class "Default")
      (node (ref "D258") (pin "2") (pinfunction "K_2") (pintype "passive"))
      (node (ref "D260") (pin "2") (pinfunction "K_2") (pintype "passive"))
      (node (ref "D262") (pin "2") (pinfunction "K_2") (pintype "passive"))
      (node (ref "D264") (pin "2") (pinfunction "K_2") (pintype "passive"))
      (node (ref "D266") (pin "2") (pinfunction "K_2") (pintype "passive"))
      (node (ref "D270") (pin "2") (pinfunction "K_2") (pintype "passive"))
    )
    (net (code "19") (name "Net-(D201-A)") (class "Default")
      (node (ref "D201") (pin "1") (pinfunction "A_1") (pintype "passive"))
      (node (ref "S201") (pin "1") (pinfunction "1_1") (pintype "passive"))
    )
    (net (code "20") (name "Net-(D202-A)") (class "Default")
      (node (ref "D202") (pin "1") (pinfunction "A_1") (pintype "passive"))
      (node (ref "S202") (pin "1") (pinfunction "1_1") (pintype "passive"))
    )
    (net (code "21") (name "Net-(D203-A)") (class "Default")
      (node (ref "D203") (pin "1") (pinfunction "A_1") (pintype "passive"))
      (node (ref "S203") (pin "1") (pinfunction "1_1") (pintype "passive"))
    )
    (net (code "22") (name "Net-(D204-A)") (class "Default")
      (node (ref "D204") (pin "1") (pinfunction "A_1") (pintype "passive"))
      (node (ref "S204") (pin "1") (pinfunction "1_1") (pintype "passive"))
    )
    (net (code "23") (name "Net-(D205-A)") (class "Default")
      (node (ref "D205") (pin "1") (pinfunction "A_1") (pintype "passive"))
      (node (ref "S205") (pin "1") (pinfunction "1_1") (pintype "passive"))
    )
    (net (code "24") (name "Net-(D206-A)") (class "Default")
      (node (ref "D206") (pin "1") (pinfunction "A_1") (pintype "passive"))
      (node (ref "S206") (pin "1") (pinfunction "1_1") (pintype "passive"))
    )
    (net (code "25") (name "Net-(D207-A)") (class "Default")
      (node (ref "D207") (pin "1") (pinfunction "A_1") (pintype "passive"))
      (node (ref "S207") (pin "1") (pinfunction "1_1") (pintype "passive"))
    )
    (net (code "26") (name "Net-(D208-A)") (class "Default")
      (node (ref "D208") (pin "1") (pinfunction "A_1") (pintype "passive"))
      (node (ref "S208") (pin "1") (pinfunction "1_1") (pintype "passive"))
    )
    (net (code "27") (name "Net-(D209-A)") (class "Default")
      (node (ref "D209") (pin "1") (pinfunction "A_1") (pintype "passive"))
      (node (ref "S209") (pin "1") (pinfunction "1_1") (pintype "passive"))
    )
    (net (code "28") (name "Net-(D210-A)") (class "Default")
      (node (ref "D210") (pin "1") (pinfunction "A_1") (pintype "passive"))
      (node (ref "S210") (pin "1") (pinfunction "1_1") (pintype "passive"))
    )
    (net (code "29") (name "Net-(D211-A)") (class "Default")
      (node (ref "D211") (pin "1") (pinfunction "A_1") (pintype "passive"))
      (node (ref "S211") (pin "1") (pinfunction "1_1") (pintype "passive"))
    )
    (net (code "30") (name "Net-(D212-A)") (class "Default")
      (node (ref "D212") (pin "1") (pinfunction "A_1") (pintype "passive"))
      (node (ref "S212") (pin "1") (pinfunction "1_1") (pintype "passive"))
    )
    (net (code "31") (name "Net-(D213-A)") (class "Default")
      (node (ref "D213") (pin "1") (pinfunction "A_1") (pintype "passive"))
      (node (ref "S213") (pin "1") (pinfunction "1_1") (pintype "passive"))
    )
    (net (code "32") (name "Net-(D214-A)") (class "Default")
      (node (ref "D214") (pin "1") (pinfunction "A_1") (pintype "passive"))
      (node (ref "S214") (pin "1") (pinfunction "1_1") (pintype "passive"))
    )
    (net (code "33") (name "Net-(D215-A)") (class "Default")
      (node (ref "D215") (pin "1") (pinfunction "A_1") (pintype "passive"))
      (node (ref "S215") (pin "1") (pinfunction "1_1") (pintype "passive"))
    )
    (net (code "34") (name "Net-(D216-A)") (class "Default")
      (node (ref "D216") (pin "1") (pinfunction "A_1") (pintype "passive"))
      (node (ref "S216") (pin "1") (pinfunction "1_1") (pintype "passive"))
    )
    (net (code "35") (name "Net-(D217-A)") (class "Default")
      (node (ref "D217") (pin "1") (pinfunction "A_1") (pintype "passive"))
      (node (ref "S217") (pin "1") (pinfunction "1_1") (pintype "passive"))
    )
    (net (code "36") (name "Net-(D218-A)") (class "Default")
      (node (ref "D218") (pin "1") (pinfunction "A_1") (pintype "passive"))
      (node (ref "S218") (pin "1") (pinfunction "1_1") (pintype "passive"))
    )
    (net (code "37") (name "Net-(D219-A)") (class "Default")
      (node (ref "D219") (pin "1") (pinfunction "A_1") (pintype "passive"))
      (node (ref "S219") (pin "1") (pinfunction "1_1") (pintype "passive"))
    )
    (net (code "38") (name "Net-(D220-A)") (class "Default")
      (node (ref "D220") (pin "1") (pinfunction "A_1") (pintype "passive"))
      (node (ref "S220") (pin "1") (pinfunction "1_1") (pintype "passive"))
    )
    (net (code "39") (name "Net-(D221-A)") (class "Default")
      (node (ref "D221") (pin "1") (pinfunction "A_1") (pintype "passive"))
      (node (ref "S221") (pin "1") (pinfunction "1_1") (pintype "passive"))
    )
    (net (code "40") (name "Net-(D222-A)") (class "Default")
      (node (ref "D222") (pin "1") (pinfunction "A_1") (pintype "passive"))
      (node (ref "S222") (pin "1") (pinfunction "1_1") (pintype "passive"))
    )
    (net (code "41") (name "Net-(D223-A)") (class "Default")
      (node (ref "D223") (pin "1") (pinfunction "A_1") (pintype "passive"))
      (node (ref "S223") (pin "1") (pinfunction "1_1") (pintype "passive"))
    )
    (net (code "42") (name "Net-(D224-A)") (class "Default")
      (node (ref "D224") (pin "1") (pinfunction "A_1") (pintype "passive"))
      (node (ref "S224") (pin "1") (pinfunction "1_1") (pintype "passive"))
    )
    (net (code "43") (name "Net-(D225-A)") (class "Default")
      (node (ref "D225") (pin "1") (pinfunction "A_1") (pintype "passive"))
      (node (ref "S225") (pin "1") (pinfunction "1_1") (pintype "passive"))
    )
    (net (code "44") (name "Net-(D226-A)") (class "Default")
      (node (ref "D226") (pin "1") (pinfunction "A_1") (pintype "passive"))
      (node (ref "S226") (pin "1") (pinfunction "1_1") (pintype "passive"))
    )
    (net (code "45") (name "Net-(D227-A)") (class "Default")
      (node (ref "D227") (pin "1") (pinfunction "A_1") (pintype "passive"))
      (node (ref "S227") (pin "1") (pinfunction "1_1") (pintype "passive"))
    )
    (net (code "46") (name "Net-(D228-A)") (class "Default")
      (node (ref "D228") (pin "1") (pinfunction "A_1") (pintype "passive"))
      (node (ref "S228") (pin "2") (pinfunction "2_2") (pintype "passive"))
    )
    (net (code "47") (name "Net-(D229-A)") (class "Default")
      (node (ref "D229") (pin "1") (pinfunction "A_1") (pintype "passive"))
      (node (ref "S229") (pin "1") (pinfunction "1_1") (pintype "passive"))
    )
    (net (code "48") (name "Net-(D230-A)") (class "Default")
      (node (ref "D230") (pin "1") (pinfunction "A_1") (pintype "passive"))
      (node (ref "S230") (pin "1") (pinfunction "1_1") (pintype "passive"))
    )
    (net (code "49") (name "Net-(D231-A)") (class "Default")
      (node (ref "D231") (pin "1") (pinfunction "A_1") (pintype "passive"))
      (node (ref "S231") (pin "1") (pinfunction "1_1") (pintype "passive"))
    )
    (net (code "50") (name "Net-(D232-A)") (class "Default")
      (node (ref "D232") (pin "1") (pinfunction "A_1") (pintype "passive"))
      (node (ref "S232") (pin "1") (pinfunction "1_1") (pintype "passive"))
    )
    (net (code "51") (name "Net-(D233-A)") (class "Default")
      (node (ref "D233") (pin "1") (pinfunction "A_1") (pintype "passive"))
      (node (ref "S233") (pin "1") (pinfunction "1_1") (pintype "passive"))
    )
    (net (code "52") (name "Net-(D234-A)") (class "Default")
      (node (ref "D234") (pin "1") (pinfunction "A_1") (pintype "passive"))
      (node (ref "S234") (pin "1") (pinfunction "1_1") (pintype "passive"))
    )
    (net (code "53") (name "Net-(D235-A)") (class "Default")
      (node (ref "D235") (pin "1") (pinfunction "A_1") (pintype "passive"))
      (node (ref "S235") (pin "1") (pinfunction "1_1") (pintype "passive"))
    )
    (net (code "54") (name "Net-(D236-A)") (class "Default")
      (node (ref "D236") (pin "1") (pinfunction "A_1") (pintype "passive"))
      (node (ref "S236") (pin "1") (pinfunction "1_1") (pintype "passive"))
    )
    (net (code "55") (name "Net-(D237-A)") (class "Default")
      (node (ref "D237") (pin "1") (pinfunction "A_1") (pintype "passive"))
      (node (ref "S237") (pin "1") (pinfunction "1_1") (pintype "passive"))
    )
    (net (code "56") (name "Net-(D238-A)") (class "Default")
      (node (ref "D238") (pin "1") (pinfunction "A_1") (pintype "passive"))
      (node (ref "S238") (pin "1") (pinfunction "1_1") (pintype "passive"))
    )
    (net (code "57") (name "Net-(D239-A)") (class "Default")
      (node (ref "D239") (pin "1") (pinfunction "A_1") (pintype "passive"))
      (node (ref "S239") (pin "1") (pinfunction "1_1") (pintype "passive"))
    )
    (net (code "58") (name "Net-(D240-A)") (class "Default")
      (node (ref "D240") (pin "1") (pinfunction "A_1") (pintype "passive"))
      (node (ref "S240") (pin "1") (pinfunction "1_1") (pintype "passive"))
    )
    (net (code "59") (name "Net-(D241-A)") (class "Default")
      (node (ref "D241") (pin "1") (pinfunction "A_1") (pintype "passive"))
      (node (ref "S241") (pin "1") (pinfunction "1_1") (pintype "passive"))
    )
    (net (code "60") (name "Net-(D242-A)") (class "Default")
      (node (ref "D242") (pin "1") (pinfunction "A_1") (pintype "passive"))
      (node (ref "S242") (pin "1") (pinfunction "1_1") (pintype "passive"))
    )
    (net (code "61") (name "Net-(D243-A)") (class "Default")
      (node (ref "D243") (pin "1") (pinfunction "A_1") (pintype "passive"))
      (node (ref "S243") (pin "1") (pinfunction "1_1") (pintype "passive"))
    )
    (net (code "62") (name "Net-(D244-A)") (class "Default")
      (node (ref "D244") (pin "1") (pinfunction "A_1") (pintype "passive"))
      (node (ref "S244") (pin "1") (pinfunction "1_1") (pintype "passive"))
    )
    (net (code "63") (name "Net-(D245-A)") (class "Default")
      (node (ref "D245") (pin "1") (pinfunction "A_1") (pintype "passive"))
      (node (ref "S245") (pin "1") (pinfunction "1_1") (pintype "passive"))
    )
    (net (code "64") (name "Net-(D246-A)") (class "Default")
      (node (ref "D246") (pin "1") (pinfunction "A_1") (pintype "passive"))
      (node (ref "S246") (pin "1") (pinfunction "1_1") (pintype "passive"))
    )
    (net (code "65") (name "Net-(D247-A)") (class "Default")
      (node (ref "D247") (pin "1") (pinfunction "A_1") (pintype "passive"))
      (node (ref "S247") (pin "1") (pinfunction "1_1") (pintype "passive"))
    )
    (net (code "66") (name "Net-(D248-A)") (class "Default")
      (node (ref "D248") (pin "1") (pinfunction "A_1") (pintype "passive"))
      (node (ref "S248") (pin "1") (pinfunction "1_1") (pintype "passive"))
    )
    (net (code "67") (name "Net-(D249-A)") (class "Default")
      (node (ref "D249") (pin "1") (pinfunction "A_1") (pintype "passive"))
      (node (ref "S249") (pin "1") (pinfunction "1_1") (pintype "passive"))
    )
    (net (code "68") (name "Net-(D250-A)") (class "Default")
      (node (ref "D250") (pin "1") (pinfunction "A_1") (pintype "passive"))
      (node (ref "S250") (pin "1") (pinfunction "1_1") (pintype "passive"))
    )
    (net (code "69") (name "Net-(D251-A)") (class "Default")
      (node (ref "D251") (pin "1") (pinfunction "A_1") (pintype "passive"))
      (node (ref "S251") (pin "1") (pinfunction "1_1") (pintype "passive"))
    )
    (net (code "70") (name "Net-(D252-A)") (class "Default")
      (node (ref "D252") (pin "1") (pinfunction "A_1") (pintype "passive"))
      (node (ref "S252") (pin "1") (pinfunction "1_1") (pintype "passive"))
    )
    (net (code "71") (name "Net-(D253-A)") (class "Default")
      (node (ref "D253") (pin "1") (pinfunction "A_1") (pintype "passive"))
      (node (ref "S253") (pin "1") (pinfunction "1_1") (pintype "passive"))
    )
    (net (code "72") (name "Net-(D254-A)") (class "Default")
      (node (ref "D254") (pin "1") (pinfunction "A_1") (pintype "passive"))
      (node (ref "S254") (pin "1") (pinfunction "1_1") (pintype "passive"))
    )
    (net (code "73") (name "Net-(D255-A)") (class "Default")
      (node (ref "D255") (pin "1") (pinfunction "A_1") (pintype "passive"))
      (node (ref "S255") (pin "1") (pinfunction "1_1") (pintype "passive"))
    )
    (net (code "74") (name "Net-(D256-A)") (class "Default")
      (node (ref "D256") (pin "1") (pinfunction "A_1") (pintype "passive"))
      (node (ref "S256") (pin "1") (pinfunction "1_1") (pintype "passive"))
    )
    (net (code "75") (name "Net-(D257-A)") (class "Default")
      (node (ref "D257") (pin "1") (pinfunction "A_1") (pintype "passive"))
      (node (ref "S257") (pin "2") (pinfunction "2_2") (pintype "passive"))
    )
    (net (code "76") (name "Net-(D258-A)") (class "Default")
      (node (ref "D258") (pin "1") (pinfunction "A_1") (pintype "passive"))
      (node (ref "S258") (pin "1") (pinfunction "1_1") (pintype "passive"))
    )
    (net (code "77") (name "Net-(D259-A)") (class "Default")
      (node (ref "D259") (pin "1") (pinfunction "A_1") (pintype "passive"))
      (node (ref "S259") (pin "1") (pinfunction "1_1") (pintype "passive"))
    )
    (net (code "78") (name "Net-(D260-A)") (class "Default")
      (node (ref "D260") (pin "1") (pinfunction "A_1") (pintype "passive"))
      (node (ref "S260") (pin "1") (pinfunction "1_1") (pintype "passive"))
    )
    (net (code "79") (name "Net-(D261-A)") (class "Default")
      (node (ref "D261") (pin "1") (pinfunction "A_1") (pintype "passive"))
      (node (ref "S261") (pin "2") (pinfunction "2_2") (pintype "passive"))
    )
    (net (code "80") (name "Net-(D262-A)") (class "Default")
      (node (ref "D262") (pin "1") (pinfunction "A_1") (pintype "passive"))
      (node (ref "S262") (pin "1") (pinfunction "1_1") (pintype "passive"))
    )
    (net (code "81") (name "Net-(D263-A)") (class "Default")
      (node (ref "D263") (pin "1") (pinfunction "A_1") (pintype "passive"))
      (node (ref "S263") (pin "1") (pinfunction "1_1") (pintype "passive"))
    )
    (net (code "82") (name "Net-(D264-A)") (class "Default")
      (node (ref "D264") (pin "1") (pinfunction "A_1") (pintype "passive"))
      (node (ref "S264") (pin "2") (pinfunction "2_2") (pintype "passive"))
    )
    (net (code "83") (name "Net-(D265-A)") (class "Default")
      (node (ref "D265") (pin "1") (pinfunction "A_1") (pintype "passive"))
      (node (ref "S265") (pin "1") (pinfunction "1_1") (pintype "passive"))
    )
    (net (code "84") (name "Net-(D266-A)") (class "Default")
      (node (ref "D266") (pin "1") (pinfunction "A_1") (pintype "passive"))
      (node (ref "S266") (pin "1") (pinfunction "1_1") (pintype "passive"))
    )
    (net (code "85") (name "Net-(D267-A)") (class "Default")
      (node (ref "D267") (pin "1") (pinfunction "A_1") (pintype "passive"))
      (node (ref "S267") (pin "2") (pinfunction "2_2") (pintype "passive"))
    )
  )
)
